# tempsensor_V3_02.net
KiCad netlist of a schematic drawn in EAGLE
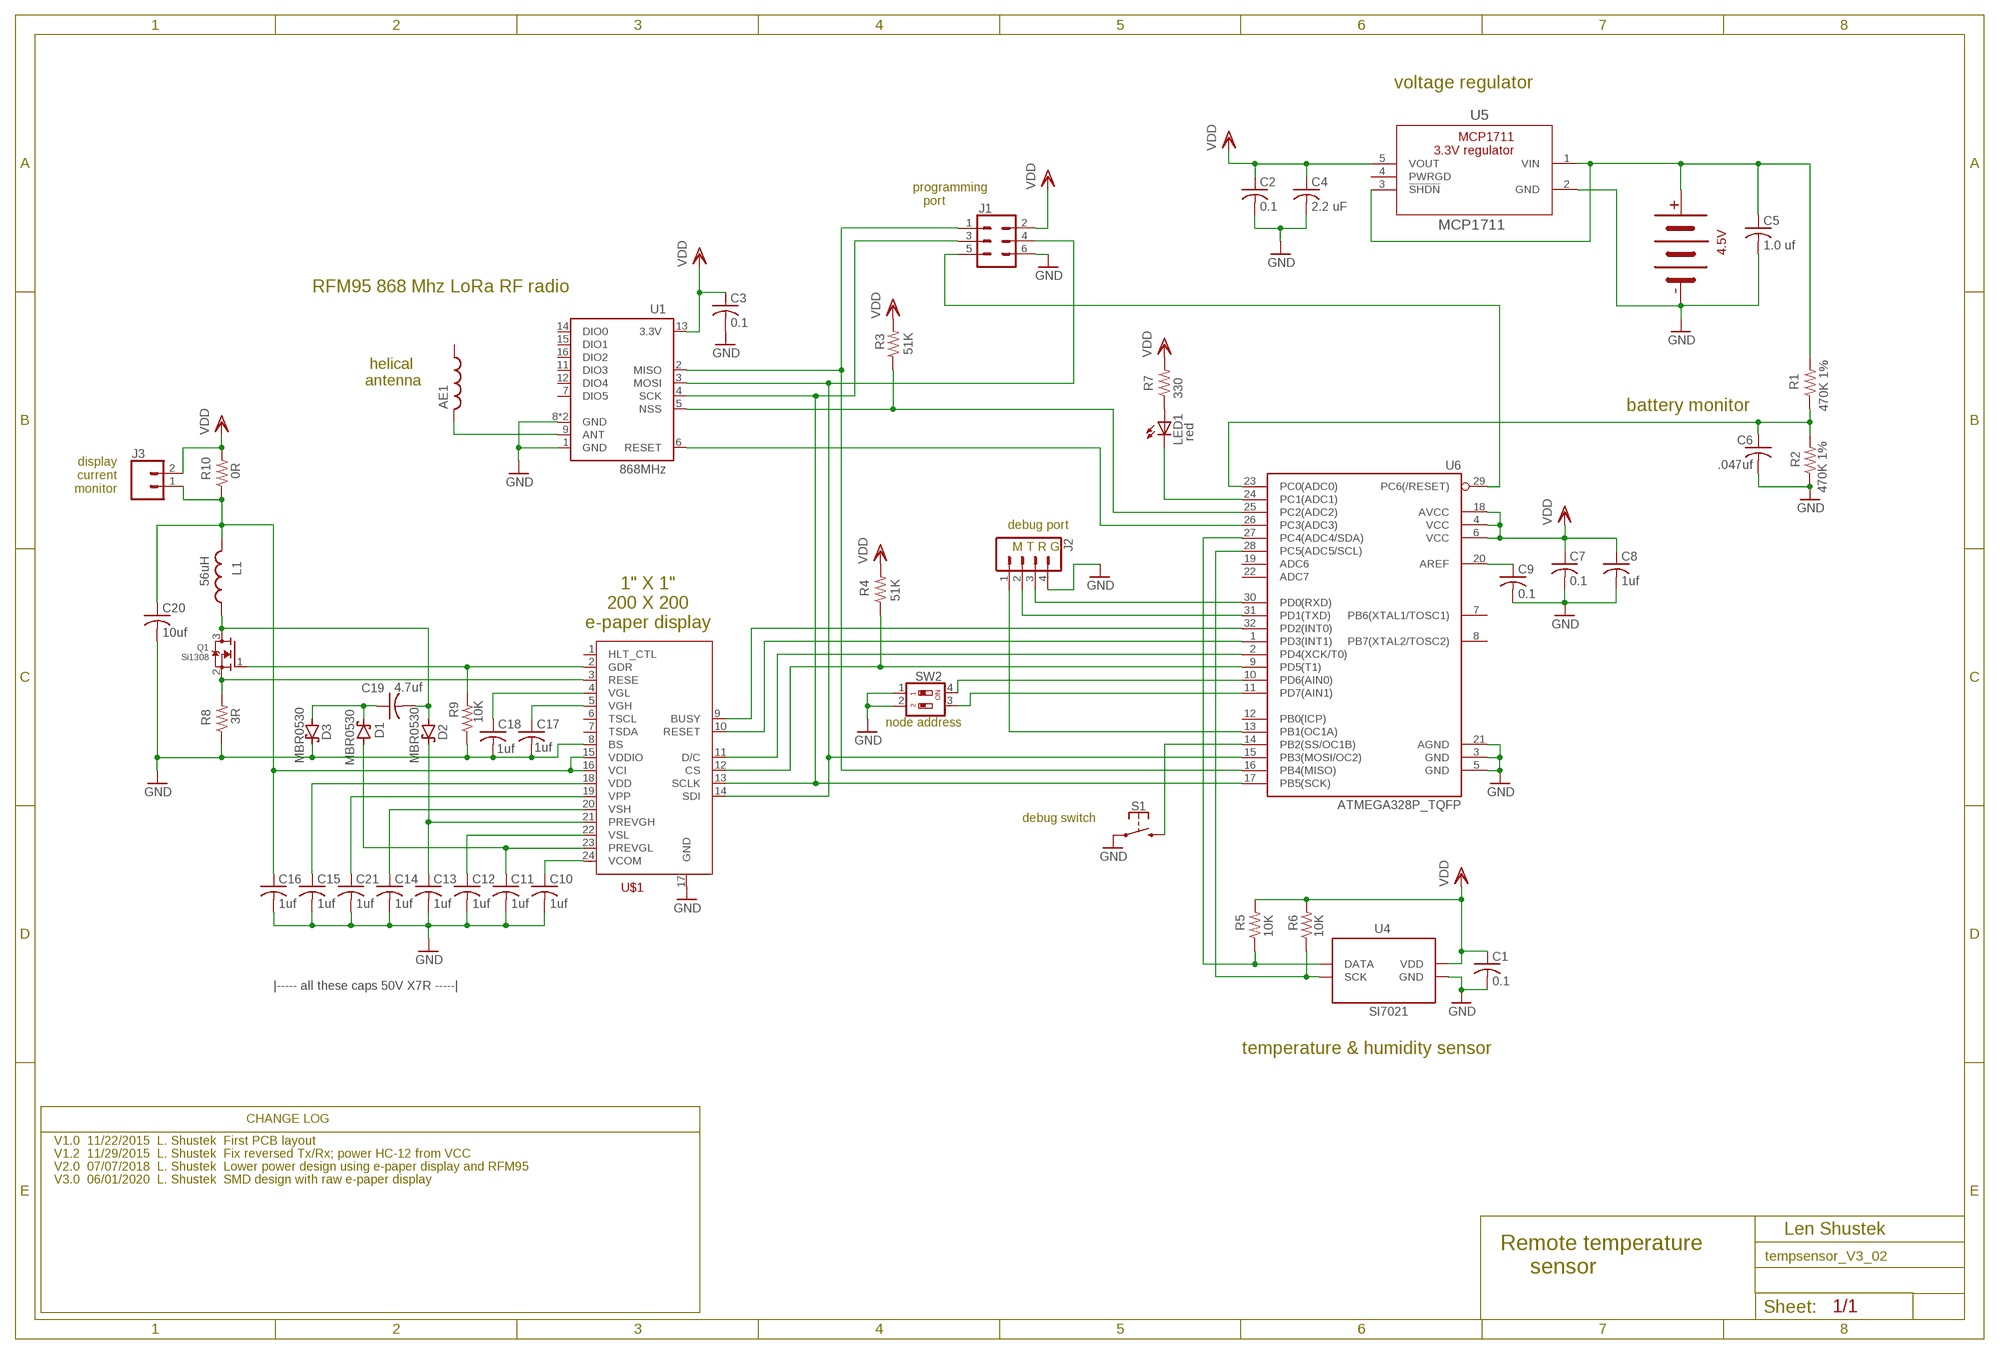
[diagram p0: schematic, sheet 1]

(export (version "E")
  (design (tool "Eeschema 10.0.6"))
  (components
    (comp (ref "AE1")
      (value "ANTENNA-HELICAL")
      (footprint "eagle-import:ANTENNA-HELICAL_PULSE_SMD")
      (libsource (lib "eagle-import") (part "ANTENNA-HELICAL"))
    )
    (comp (ref "B1")
      (value "3PC-BATTERY-HOLDER")
      (footprint "eagle-import:3AAA-BATTERY-HOLDER")
      (libsource (lib "eagle-import") (part "3PC-BATTERY-HOLDER"))
    )
    (comp (ref "C1")
      (value "0.1")
      (footprint "eagle-import:C0805")
      (libsource (lib "eagle-import") (part "C-USC0805"))
    )
    (comp (ref "C2")
      (value "0.1")
      (footprint "eagle-import:C0805")
      (libsource (lib "eagle-import") (part "C-USC0805"))
    )
    (comp (ref "C3")
      (value "0.1")
      (footprint "eagle-import:C0805")
      (libsource (lib "eagle-import") (part "C-USC0805"))
    )
    (comp (ref "C4")
      (value "2.2 uF")
      (footprint "eagle-import:C1210")
      (libsource (lib "eagle-import") (part "C-USC1210"))
    )
    (comp (ref "C5")
      (value "1.0 uf")
      (footprint "eagle-import:C0805")
      (libsource (lib "eagle-import") (part "C-USC0805"))
    )
    (comp (ref "C6")
      (value ".047uf")
      (footprint "eagle-import:C0805")
      (libsource (lib "eagle-import") (part "C-USC0805"))
    )
    (comp (ref "C7")
      (value "0.1")
      (footprint "eagle-import:C0805")
      (libsource (lib "eagle-import") (part "C-USC0805"))
    )
    (comp (ref "C8")
      (value "1uf")
      (footprint "eagle-import:C0805")
      (libsource (lib "eagle-import") (part "C-USC0805"))
    )
    (comp (ref "C9")
      (value "0.1")
      (footprint "eagle-import:C0805")
      (libsource (lib "eagle-import") (part "C-USC0805"))
    )
    (comp (ref "C10")
      (value "1uf")
      (footprint "eagle-import:C0805")
      (libsource (lib "eagle-import") (part "C-USC0805"))
    )
    (comp (ref "C11")
      (value "1uf")
      (footprint "eagle-import:C0805")
      (libsource (lib "eagle-import") (part "C-USC0805"))
    )
    (comp (ref "C12")
      (value "1uf")
      (footprint "eagle-import:C0805")
      (libsource (lib "eagle-import") (part "C-USC0805"))
    )
    (comp (ref "C13")
      (value "1uf")
      (footprint "eagle-import:C0805")
      (libsource (lib "eagle-import") (part "C-USC0805"))
    )
    (comp (ref "C14")
      (value "1uf")
      (footprint "eagle-import:C0805")
      (libsource (lib "eagle-import") (part "C-USC0805"))
    )
    (comp (ref "C15")
      (value "1uf")
      (footprint "eagle-import:C0805")
      (libsource (lib "eagle-import") (part "C-USC0805"))
    )
    (comp (ref "C16")
      (value "1uf")
      (footprint "eagle-import:C0805")
      (libsource (lib "eagle-import") (part "C-USC0805"))
    )
    (comp (ref "C17")
      (value "1uf")
      (footprint "eagle-import:C0805")
      (libsource (lib "eagle-import") (part "C-USC0805"))
    )
    (comp (ref "C18")
      (value "1uf")
      (footprint "eagle-import:C0805")
      (libsource (lib "eagle-import") (part "C-USC0805"))
    )
    (comp (ref "C19")
      (value "4.7uf")
      (footprint "eagle-import:C1210")
      (libsource (lib "eagle-import") (part "C-USC1210"))
    )
    (comp (ref "C20")
      (value "10uf")
      (footprint "eagle-import:C1210")
      (libsource (lib "eagle-import") (part "C-USC1210"))
    )
    (comp (ref "C21")
      (value "1uf")
      (footprint "eagle-import:C0805")
      (libsource (lib "eagle-import") (part "C-USC0805"))
    )
    (comp (ref "D1")
      (value "MBR0530")
      (footprint "eagle-import:SOD123-2")
      (libsource (lib "eagle-import") (part "DIODE,SCHOTTKY"))
    )
    (comp (ref "D2")
      (value "MBR0530")
      (footprint "eagle-import:SOD123-2")
      (libsource (lib "eagle-import") (part "DIODE,SCHOTTKY"))
    )
    (comp (ref "D3")
      (value "MBR0530")
      (footprint "eagle-import:SOD123-2")
      (libsource (lib "eagle-import") (part "DIODE,SCHOTTKY"))
    )
    (comp (ref "J1")
      (value "CONN_2X3")
      (footprint "eagle-import:2X3_SMT_RTANGLE_OUTLINE")
      (libsource (lib "eagle-import") (part "CONN_2X3"))
    )
    (comp (ref "J2")
      (value "CONN_04")
      (footprint "eagle-import:1X04")
      (libsource (lib "eagle-import") (part "CONN_04"))
    )
    (comp (ref "J3")
      (value "CONN_02")
      (footprint "eagle-import:1X02")
      (libsource (lib "eagle-import") (part "CONN_02"))
    )
    (comp (ref "L1")
      (value "56uH")
      (footprint "eagle-import:L1812")
      (libsource (lib "eagle-import") (part "L-USL1812"))
    )
    (comp (ref "LED1")
      (value "red")
      (footprint "eagle-import:LED_PLCC-2")
      (libsource (lib "eagle-import") (part "LEDPLCC-2"))
    )
    (comp (ref "Q1")
      (value "Si1308")
      (footprint "eagle-import:SC70-3-R")
      (libsource (lib "eagle-import") (part "MOSFET-NSC70-3-SMT"))
    )
    (comp (ref "R1")
      (value "470K 1%")
      (footprint "eagle-import:M0805")
      (libsource (lib "eagle-import") (part "R-US_M0805"))
    )
    (comp (ref "R2")
      (value "470K 1%")
      (footprint "eagle-import:M0805")
      (libsource (lib "eagle-import") (part "R-US_M0805"))
    )
    (comp (ref "R3")
      (value "51K")
      (footprint "eagle-import:M0805")
      (libsource (lib "eagle-import") (part "R-US_M0805"))
    )
    (comp (ref "R4")
      (value "51K")
      (footprint "eagle-import:M0805")
      (libsource (lib "eagle-import") (part "R-US_M0805"))
    )
    (comp (ref "R5")
      (value "10K")
      (footprint "eagle-import:M0805")
      (libsource (lib "eagle-import") (part "R-US_M0805"))
    )
    (comp (ref "R6")
      (value "10K")
      (footprint "eagle-import:M0805")
      (libsource (lib "eagle-import") (part "R-US_M0805"))
    )
    (comp (ref "R7")
      (value "330")
      (footprint "eagle-import:M0805")
      (libsource (lib "eagle-import") (part "R-US_M0805"))
    )
    (comp (ref "R8")
      (value "3R")
      (footprint "eagle-import:M0805")
      (libsource (lib "eagle-import") (part "R-US_M0805"))
    )
    (comp (ref "R9")
      (value "10K")
      (footprint "eagle-import:M0805")
      (libsource (lib "eagle-import") (part "R-US_M0805"))
    )
    (comp (ref "R10")
      (value "0R")
      (footprint "eagle-import:M0805")
      (libsource (lib "eagle-import") (part "R-US_M0805"))
    )
    (comp (ref "S1")
      (value "PUSHBUTTON-SPSTSWITCH_C&K_GULLWING_5MM")
      (footprint "eagle-import:SWITCH_C&K_GULLWING_5MM")
      (libsource (lib "eagle-import") (part "PUSHBUTTON-SPSTSWITCH_C&K_GULLWING_5MM"))
    )
    (comp (ref "SW2")
      (value "SWITCH-2POS-DIP")
      (footprint "eagle-import:SMS-002")
      (libsource (lib "eagle-import") (part "SWITCH-2POS-DIP"))
    )
    (comp (ref "U$1")
      (value "E-PAPER-DISPLAYMOLEX")
      (footprint "eagle-import:MOLEX_50511")
      (libsource (lib "eagle-import") (part "E-PAPER-DISPLAYMOLEX"))
    )
    (comp (ref "U1")
      (value "868MHz")
      (footprint "eagle-import:RFM69HCW-XXXS2")
      (libsource (lib "eagle-import") (part "RFM69HCW-915"))
    )
    (comp (ref "U4")
      (value "SI7021")
      (footprint "eagle-import:DFN-6-3X3-SI7021")
      (libsource (lib "eagle-import") (part "SI7021"))
    )
    (comp (ref "U5")
      (value "MCP1711")
      (footprint "eagle-import:SOT-23-5")
      (fields (field (name "MANUFACTURER_PART_NUMBER") "mcp1754"))
      (libsource (lib "eagle-import") (part "MCP1711"))
    )
    (comp (ref "U6")
      (value "ATMEGA328P_TQFP")
      (footprint "eagle-import:TQFP32-08")
      (libsource (lib "eagle-import") (part "ATMEGA328P_TQFP"))
    )
  )
  (nets
    (net (code "1") (name "/PWRGD") (class "Default")
      (node (ref "U5") (pin "4") (pinfunction "PWRGD_4") (pintype "power_in"))
    )
    (net (code "2") (name "GND") (class "Default")
      (node (ref "B1") (pin "P$1") (pinfunction "P$1_P$1") (pintype "bidirectional"))
      (node (ref "C1") (pin "2") (pinfunction "2_2") (pintype "passive"))
      (node (ref "C10") (pin "2") (pinfunction "2_2") (pintype "passive"))
      (node (ref "C11") (pin "2") (pinfunction "2_2") (pintype "passive"))
      (node (ref "C12") (pin "2") (pinfunction "2_2") (pintype "passive"))
      (node (ref "C13") (pin "2") (pinfunction "2_2") (pintype "passive"))
      (node (ref "C14") (pin "2") (pinfunction "2_2") (pintype "passive"))
      (node (ref "C15") (pin "2") (pinfunction "2_2") (pintype "passive"))
      (node (ref "C16") (pin "2") (pinfunction "2_2") (pintype "passive"))
      (node (ref "C17") (pin "2") (pinfunction "2_2") (pintype "passive"))
      (node (ref "C18") (pin "2") (pinfunction "2_2") (pintype "passive"))
      (node (ref "C2") (pin "2") (pinfunction "2_2") (pintype "passive"))
      (node (ref "C20") (pin "2") (pinfunction "2_2") (pintype "passive"))
      (node (ref "C21") (pin "2") (pinfunction "2_2") (pintype "passive"))
      (node (ref "C3") (pin "2") (pinfunction "2_2") (pintype "passive"))
      (node (ref "C4") (pin "2") (pinfunction "2_2") (pintype "passive"))
      (node (ref "C5") (pin "2") (pinfunction "2_2") (pintype "passive"))
      (node (ref "C6") (pin "2") (pinfunction "2_2") (pintype "passive"))
      (node (ref "C7") (pin "2") (pinfunction "2_2") (pintype "passive"))
      (node (ref "C8") (pin "2") (pinfunction "2_2") (pintype "passive"))
      (node (ref "C9") (pin "2") (pinfunction "2_2") (pintype "passive"))
      (node (ref "D3") (pin "P$2") (pinfunction "C_P$2") (pintype "passive"))
      (node (ref "J1") (pin "6") (pinfunction "6_6") (pintype "bidirectional"))
      (node (ref "J2") (pin "4") (pinfunction "4_4") (pintype "passive"))
      (node (ref "R2") (pin "1") (pinfunction "1_1") (pintype "passive"))
      (node (ref "R8") (pin "1") (pinfunction "1_1") (pintype "passive"))
      (node (ref "R9") (pin "1") (pinfunction "1_1") (pintype "passive"))
      (node (ref "S1") (pin "P$1") (pinfunction "1_P$1") (pintype "passive"))
      (node (ref "S1") (pin "P$2") (pinfunction "1_P$2") (pintype "passive"))
      (node (ref "SW2") (pin "1") (pinfunction "1_1") (pintype "passive"))
      (node (ref "SW2") (pin "2") (pinfunction "2_2") (pintype "passive"))
      (node (ref "U$1") (pin "17") (pinfunction "GND_17") (pintype "bidirectional"))
      (node (ref "U$1") (pin "8") (pinfunction "BS_8") (pintype "bidirectional"))
      (node (ref "U1") (pin "1") (pinfunction "GND_1") (pintype "power_in"))
      (node (ref "U1") (pin "10") (pinfunction "GND_10") (pintype "power_in"))
      (node (ref "U1") (pin "8") (pinfunction "GND_8") (pintype "power_in"))
      (node (ref "U4") (pin "GND") (pinfunction "GND_GND") (pintype "power_in"))
      (node (ref "U5") (pin "2") (pinfunction "GND_2") (pintype "power_in"))
      (node (ref "U6") (pin "21") (pinfunction "AGND_21") (pintype "bidirectional"))
      (node (ref "U6") (pin "3") (pinfunction "GND_3") (pintype "bidirectional"))
      (node (ref "U6") (pin "5") (pinfunction "GND_5") (pintype "bidirectional"))
    )
    (net (code "3") (name "Net-(D1-A)") (class "Default")
      (node (ref "C11") (pin "1") (pinfunction "1_1") (pintype "passive"))
      (node (ref "D1") (pin "P$1") (pinfunction "A_P$1") (pintype "passive"))
      (node (ref "U$1") (pin "23") (pinfunction "PREVGL_23") (pintype "bidirectional"))
    )
    (net (code "4") (name "Net-(D1-C)") (class "Default")
      (node (ref "C19") (pin "1") (pinfunction "1_1") (pintype "passive"))
      (node (ref "D1") (pin "P$2") (pinfunction "C_P$2") (pintype "passive"))
      (node (ref "D3") (pin "P$1") (pinfunction "A_P$1") (pintype "passive"))
    )
    (net (code "5") (name "Net-(D2-A)") (class "Default")
      (node (ref "C19") (pin "2") (pinfunction "2_2") (pintype "passive"))
      (node (ref "D2") (pin "P$1") (pinfunction "A_P$1") (pintype "passive"))
      (node (ref "L1") (pin "1") (pinfunction "1_1") (pintype "passive"))
      (node (ref "Q1") (pin "3") (pinfunction "D_3") (pintype "bidirectional"))
    )
    (net (code "6") (name "Net-(D2-C)") (class "Default")
      (node (ref "C13") (pin "1") (pinfunction "1_1") (pintype "passive"))
      (node (ref "D2") (pin "P$2") (pinfunction "C_P$2") (pintype "passive"))
      (node (ref "U$1") (pin "21") (pinfunction "PREVGH_21") (pintype "bidirectional"))
    )
    (net (code "7") (name "Net-(LED1-A)") (class "Default")
      (node (ref "LED1") (pin "P$1") (pinfunction "A_P$1") (pintype "passive"))
      (node (ref "R7") (pin "1") (pinfunction "1_1") (pintype "passive"))
    )
    (net (code "8") (name "Net-(LED1-C)") (class "Default")
      (node (ref "LED1") (pin "P$2") (pinfunction "C_P$2") (pintype "passive"))
      (node (ref "U6") (pin "24") (pinfunction "PC1(ADC1)_24") (pintype "bidirectional"))
    )
    (net (code "9") (name "Net-(Q1-G)") (class "Default")
      (node (ref "Q1") (pin "1") (pinfunction "G_1") (pintype "bidirectional"))
      (node (ref "R9") (pin "2") (pinfunction "2_2") (pintype "passive"))
      (node (ref "U$1") (pin "2") (pinfunction "GDR_2") (pintype "bidirectional"))
    )
    (net (code "10") (name "Net-(Q1-S)") (class "Default")
      (node (ref "Q1") (pin "2") (pinfunction "S_2") (pintype "bidirectional"))
      (node (ref "R8") (pin "2") (pinfunction "2_2") (pintype "passive"))
      (node (ref "U$1") (pin "3") (pinfunction "RESE_3") (pintype "bidirectional"))
    )
    (net (code "11") (name "Net-(U$1-BUSY)") (class "Default")
      (node (ref "U$1") (pin "9") (pinfunction "BUSY_9") (pintype "bidirectional"))
      (node (ref "U6") (pin "32") (pinfunction "PD2(INT0)_32") (pintype "bidirectional"))
    )
    (net (code "12") (name "Net-(U$1-CS)") (class "Default")
      (node (ref "R4") (pin "1") (pinfunction "1_1") (pintype "passive"))
      (node (ref "U$1") (pin "12") (pinfunction "CS_12") (pintype "bidirectional"))
      (node (ref "U6") (pin "9") (pinfunction "PD5(T1)_9") (pintype "bidirectional"))
    )
    (net (code "13") (name "Net-(U$1-D{slash}C)") (class "Default")
      (node (ref "U$1") (pin "11") (pinfunction "D/C_11") (pintype "bidirectional"))
      (node (ref "U6") (pin "2") (pinfunction "PD4(XCK/T0)_2") (pintype "bidirectional"))
    )
    (net (code "14") (name "Net-(U$1-RESET)") (class "Default")
      (node (ref "U$1") (pin "10") (pinfunction "RESET_10") (pintype "bidirectional"))
      (node (ref "U6") (pin "1") (pinfunction "PD3(INT1)_1") (pintype "bidirectional"))
    )
    (net (code "15") (name "Net-(U$1-SCLK)") (class "Default")
      (node (ref "J1") (pin "3") (pinfunction "3_3") (pintype "bidirectional"))
      (node (ref "U$1") (pin "13") (pinfunction "SCLK_13") (pintype "bidirectional"))
      (node (ref "U1") (pin "4") (pinfunction "SCK_4") (pintype "input"))
      (node (ref "U6") (pin "17") (pinfunction "PB5(SCK)_17") (pintype "bidirectional"))
    )
    (net (code "16") (name "Net-(U$1-SDI)") (class "Default")
      (node (ref "J1") (pin "4") (pinfunction "4_4") (pintype "bidirectional"))
      (node (ref "U$1") (pin "14") (pinfunction "SDI_14") (pintype "bidirectional"))
      (node (ref "U1") (pin "3") (pinfunction "MOSI_3") (pintype "input"))
      (node (ref "U6") (pin "15") (pinfunction "PB3(MOSI/OC2)_15") (pintype "bidirectional"))
    )
    (net (code "17") (name "Net-(U$1-VCI)") (class "Default")
      (node (ref "C16") (pin "1") (pinfunction "1_1") (pintype "passive"))
      (node (ref "C20") (pin "1") (pinfunction "1_1") (pintype "passive"))
      (node (ref "J3") (pin "1") (pinfunction "1_1") (pintype "passive"))
      (node (ref "L1") (pin "2") (pinfunction "2_2") (pintype "passive"))
      (node (ref "R10") (pin "1") (pinfunction "1_1") (pintype "passive"))
      (node (ref "U$1") (pin "15") (pinfunction "VDDIO_15") (pintype "bidirectional"))
      (node (ref "U$1") (pin "16") (pinfunction "VCI_16") (pintype "bidirectional"))
    )
    (net (code "18") (name "Net-(U$1-VCOM)") (class "Default")
      (node (ref "C10") (pin "1") (pinfunction "1_1") (pintype "passive"))
      (node (ref "U$1") (pin "24") (pinfunction "VCOM_24") (pintype "bidirectional"))
    )
    (net (code "19") (name "Net-(U$1-VDD)") (class "Default")
      (node (ref "C15") (pin "1") (pinfunction "1_1") (pintype "passive"))
      (node (ref "U$1") (pin "18") (pinfunction "VDD_18") (pintype "bidirectional"))
    )
    (net (code "20") (name "Net-(U$1-VGH)") (class "Default")
      (node (ref "C17") (pin "1") (pinfunction "1_1") (pintype "passive"))
      (node (ref "U$1") (pin "5") (pinfunction "VGH_5") (pintype "bidirectional"))
    )
    (net (code "21") (name "Net-(U$1-VGL)") (class "Default")
      (node (ref "C18") (pin "1") (pinfunction "1_1") (pintype "passive"))
      (node (ref "U$1") (pin "4") (pinfunction "VGL_4") (pintype "bidirectional"))
    )
    (net (code "22") (name "Net-(U$1-VPP)") (class "Default")
      (node (ref "C21") (pin "1") (pinfunction "1_1") (pintype "passive"))
      (node (ref "U$1") (pin "19") (pinfunction "VPP_19") (pintype "bidirectional"))
    )
    (net (code "23") (name "Net-(U$1-VSH)") (class "Default")
      (node (ref "C14") (pin "1") (pinfunction "1_1") (pintype "passive"))
      (node (ref "U$1") (pin "20") (pinfunction "VSH_20") (pintype "bidirectional"))
    )
    (net (code "24") (name "Net-(U$1-VSL)") (class "Default")
      (node (ref "C12") (pin "1") (pinfunction "1_1") (pintype "passive"))
      (node (ref "U$1") (pin "22") (pinfunction "VSL_22") (pintype "bidirectional"))
    )
    (net (code "25") (name "Net-(U1-ANT)") (class "Default")
      (node (ref "AE1") (pin "P$1") (pinfunction "P$1_P$1") (pintype "bidirectional"))
      (node (ref "U1") (pin "9") (pinfunction "ANT_9") (pintype "passive"))
    )
    (net (code "26") (name "Net-(U1-MISO)") (class "Default")
      (node (ref "J1") (pin "1") (pinfunction "1_1") (pintype "bidirectional"))
      (node (ref "U1") (pin "2") (pinfunction "MISO_2") (pintype "bidirectional"))
      (node (ref "U6") (pin "16") (pinfunction "PB4(MISO)_16") (pintype "bidirectional"))
    )
    (net (code "27") (name "Net-(U1-NSS)") (class "Default")
      (node (ref "R3") (pin "1") (pinfunction "1_1") (pintype "passive"))
      (node (ref "U1") (pin "5") (pinfunction "NSS_5") (pintype "input"))
      (node (ref "U6") (pin "25") (pinfunction "PC2(ADC2)_25") (pintype "bidirectional"))
    )
    (net (code "28") (name "Net-(U1-RESET)") (class "Default")
      (node (ref "U1") (pin "6") (pinfunction "RESET_6") (pintype "input"))
      (node (ref "U6") (pin "26") (pinfunction "PC3(ADC3)_26") (pintype "bidirectional"))
    )
    (net (code "29") (name "Net-(U5-VIN)") (class "Default")
      (node (ref "B1") (pin "P$2") (pinfunction "P$2_P$2") (pintype "bidirectional"))
      (node (ref "C5") (pin "1") (pinfunction "1_1") (pintype "passive"))
      (node (ref "R1") (pin "2") (pinfunction "2_2") (pintype "passive"))
      (node (ref "U5") (pin "1") (pinfunction "VIN_1") (pintype "input"))
      (node (ref "U5") (pin "3") (pinfunction "~{SHDN}_3") (pintype "passive"))
    )
    (net (code "30") (name "Net-(U6-AREF)") (class "Default")
      (node (ref "C9") (pin "1") (pinfunction "1_1") (pintype "passive"))
      (node (ref "U6") (pin "20") (pinfunction "AREF_20") (pintype "bidirectional"))
    )
    (net (code "31") (name "Net-(U6-PB1(OC1A))") (class "Default")
      (node (ref "J2") (pin "1") (pinfunction "1_1") (pintype "passive"))
      (node (ref "U6") (pin "13") (pinfunction "PB1(OC1A)_13") (pintype "bidirectional"))
    )
    (net (code "32") (name "Net-(U6-PB2(SS{slash}OC1B))") (class "Default")
      (node (ref "S1") (pin "P$3") (pinfunction "3_P$3") (pintype "passive"))
      (node (ref "S1") (pin "P$4") (pinfunction "3_P$4") (pintype "passive"))
      (node (ref "U6") (pin "14") (pinfunction "PB2(SS/OC1B)_14") (pintype "bidirectional"))
    )
    (net (code "33") (name "Net-(U6-PC0(ADC0))") (class "Default")
      (node (ref "C6") (pin "1") (pinfunction "1_1") (pintype "passive"))
      (node (ref "R1") (pin "1") (pinfunction "1_1") (pintype "passive"))
      (node (ref "R2") (pin "2") (pinfunction "2_2") (pintype "passive"))
      (node (ref "U6") (pin "23") (pinfunction "PC0(ADC0)_23") (pintype "bidirectional"))
    )
    (net (code "34") (name "Net-(U6-PC4(ADC4{slash}SDA))") (class "Default")
      (node (ref "R5") (pin "1") (pinfunction "1_1") (pintype "passive"))
      (node (ref "U4") (pin "DATA") (pinfunction "DATA_DATA") (pintype "bidirectional"))
      (node (ref "U6") (pin "27") (pinfunction "PC4(ADC4/SDA)_27") (pintype "bidirectional"))
    )
    (net (code "35") (name "Net-(U6-PC5(ADC5{slash}SCL))") (class "Default")
      (node (ref "R6") (pin "1") (pinfunction "1_1") (pintype "passive"))
      (node (ref "U4") (pin "SCK") (pinfunction "SCK_SCK") (pintype "input"))
      (node (ref "U6") (pin "28") (pinfunction "PC5(ADC5/SCL)_28") (pintype "bidirectional"))
    )
    (net (code "36") (name "Net-(U6-PC6({slash}RESET))") (class "Default")
      (node (ref "J1") (pin "5") (pinfunction "5_5") (pintype "bidirectional"))
      (node (ref "U6") (pin "29") (pinfunction "PC6(/RESET)_29") (pintype "bidirectional"))
    )
    (net (code "37") (name "Net-(U6-PD0(RXD))") (class "Default")
      (node (ref "J2") (pin "3") (pinfunction "3_3") (pintype "passive"))
      (node (ref "U6") (pin "30") (pinfunction "PD0(RXD)_30") (pintype "bidirectional"))
    )
    (net (code "38") (name "Net-(U6-PD1(TXD))") (class "Default")
      (node (ref "J2") (pin "2") (pinfunction "2_2") (pintype "passive"))
      (node (ref "U6") (pin "31") (pinfunction "PD1(TXD)_31") (pintype "bidirectional"))
    )
    (net (code "39") (name "Net-(U6-PD6(AIN0))") (class "Default")
      (node (ref "SW2") (pin "4") (pinfunction "4_4") (pintype "passive"))
      (node (ref "U6") (pin "10") (pinfunction "PD6(AIN0)_10") (pintype "bidirectional"))
    )
    (net (code "40") (name "Net-(U6-PD7(AIN1))") (class "Default")
      (node (ref "SW2") (pin "3") (pinfunction "3_3") (pintype "passive"))
      (node (ref "U6") (pin "11") (pinfunction "PD7(AIN1)_11") (pintype "bidirectional"))
    )
    (net (code "41") (name "VDD") (class "Default")
      (node (ref "C1") (pin "1") (pinfunction "1_1") (pintype "passive"))
      (node (ref "C2") (pin "1") (pinfunction "1_1") (pintype "passive"))
      (node (ref "C3") (pin "1") (pinfunction "1_1") (pintype "passive"))
      (node (ref "C4") (pin "1") (pinfunction "1_1") (pintype "passive"))
      (node (ref "C7") (pin "1") (pinfunction "1_1") (pintype "passive"))
      (node (ref "C8") (pin "1") (pinfunction "1_1") (pintype "passive"))
      (node (ref "J1") (pin "2") (pinfunction "2_2") (pintype "bidirectional"))
      (node (ref "J3") (pin "2") (pinfunction "2_2") (pintype "passive"))
      (node (ref "R10") (pin "2") (pinfunction "2_2") (pintype "passive"))
      (node (ref "R3") (pin "2") (pinfunction "2_2") (pintype "passive"))
      (node (ref "R4") (pin "2") (pinfunction "2_2") (pintype "passive"))
      (node (ref "R5") (pin "2") (pinfunction "2_2") (pintype "passive"))
      (node (ref "R6") (pin "2") (pinfunction "2_2") (pintype "passive"))
      (node (ref "R7") (pin "2") (pinfunction "2_2") (pintype "passive"))
      (node (ref "U1") (pin "13") (pinfunction "3.3V_13") (pintype "power_in"))
      (node (ref "U4") (pin "VDD") (pinfunction "VDD_VDD") (pintype "power_in"))
      (node (ref "U5") (pin "5") (pinfunction "VOUT_5") (pintype "output"))
      (node (ref "U6") (pin "18") (pinfunction "AVCC_18") (pintype "bidirectional"))
      (node (ref "U6") (pin "4") (pinfunction "VCC_4") (pintype "bidirectional"))
      (node (ref "U6") (pin "6") (pinfunction "VCC_6") (pintype "bidirectional"))
    )
    (net (code "42") (name "unconnected-(AE1-PadP$2)") (class "Default")
      (node (ref "AE1") (pin "P$2") (pinfunction "P$2_P$2") (pintype "bidirectional"))
    )
    (net (code "43") (name "unconnected-(U$1-HLT_CTL-Pad1)") (class "Default")
      (node (ref "U$1") (pin "1") (pinfunction "HLT_CTL_1") (pintype "bidirectional"))
    )
    (net (code "44") (name "unconnected-(U$1-TSCL-Pad6)") (class "Default")
      (node (ref "U$1") (pin "6") (pinfunction "TSCL_6") (pintype "bidirectional"))
    )
    (net (code "45") (name "unconnected-(U$1-TSDA-Pad7)") (class "Default")
      (node (ref "U$1") (pin "7") (pinfunction "TSDA_7") (pintype "bidirectional"))
    )
    (net (code "46") (name "unconnected-(U1-DIO0-Pad14)") (class "Default")
      (node (ref "U1") (pin "14") (pinfunction "DIO0_14") (pintype "bidirectional"))
    )
    (net (code "47") (name "unconnected-(U1-DIO1-Pad15)") (class "Default")
      (node (ref "U1") (pin "15") (pinfunction "DIO1_15") (pintype "bidirectional"))
    )
    (net (code "48") (name "unconnected-(U1-DIO2-Pad16)") (class "Default")
      (node (ref "U1") (pin "16") (pinfunction "DIO2_16") (pintype "bidirectional"))
    )
    (net (code "49") (name "unconnected-(U1-DIO3-Pad11)") (class "Default")
      (node (ref "U1") (pin "11") (pinfunction "DIO3_11") (pintype "bidirectional"))
    )
    (net (code "50") (name "unconnected-(U1-DIO4-Pad12)") (class "Default")
      (node (ref "U1") (pin "12") (pinfunction "DIO4_12") (pintype "bidirectional"))
    )
    (net (code "51") (name "unconnected-(U1-DIO5-Pad7)") (class "Default")
      (node (ref "U1") (pin "7") (pinfunction "DIO5_7") (pintype "bidirectional"))
    )
    (net (code "52") (name "unconnected-(U6-ADC6-Pad19)") (class "Default")
      (node (ref "U6") (pin "19") (pinfunction "ADC6_19") (pintype "bidirectional"))
    )
    (net (code "53") (name "unconnected-(U6-ADC7-Pad22)") (class "Default")
      (node (ref "U6") (pin "22") (pinfunction "ADC7_22") (pintype "bidirectional"))
    )
    (net (code "54") (name "unconnected-(U6-PB0(ICP)-Pad12)") (class "Default")
      (node (ref "U6") (pin "12") (pinfunction "PB0(ICP)_12") (pintype "bidirectional"))
    )
    (net (code "55") (name "unconnected-(U6-PB6(XTAL1{slash}TOSC1)-Pad7)") (class "Default")
      (node (ref "U6") (pin "7") (pinfunction "PB6(XTAL1/TOSC1)_7") (pintype "bidirectional"))
    )
    (net (code "56") (name "unconnected-(U6-PB7(XTAL2{slash}TOSC2)-Pad8)") (class "Default")
      (node (ref "U6") (pin "8") (pinfunction "PB7(XTAL2/TOSC2)_8") (pintype "bidirectional"))
    )
  )
)
